# isp_02.net
KiCad netlist of a schematic drawn in EAGLE
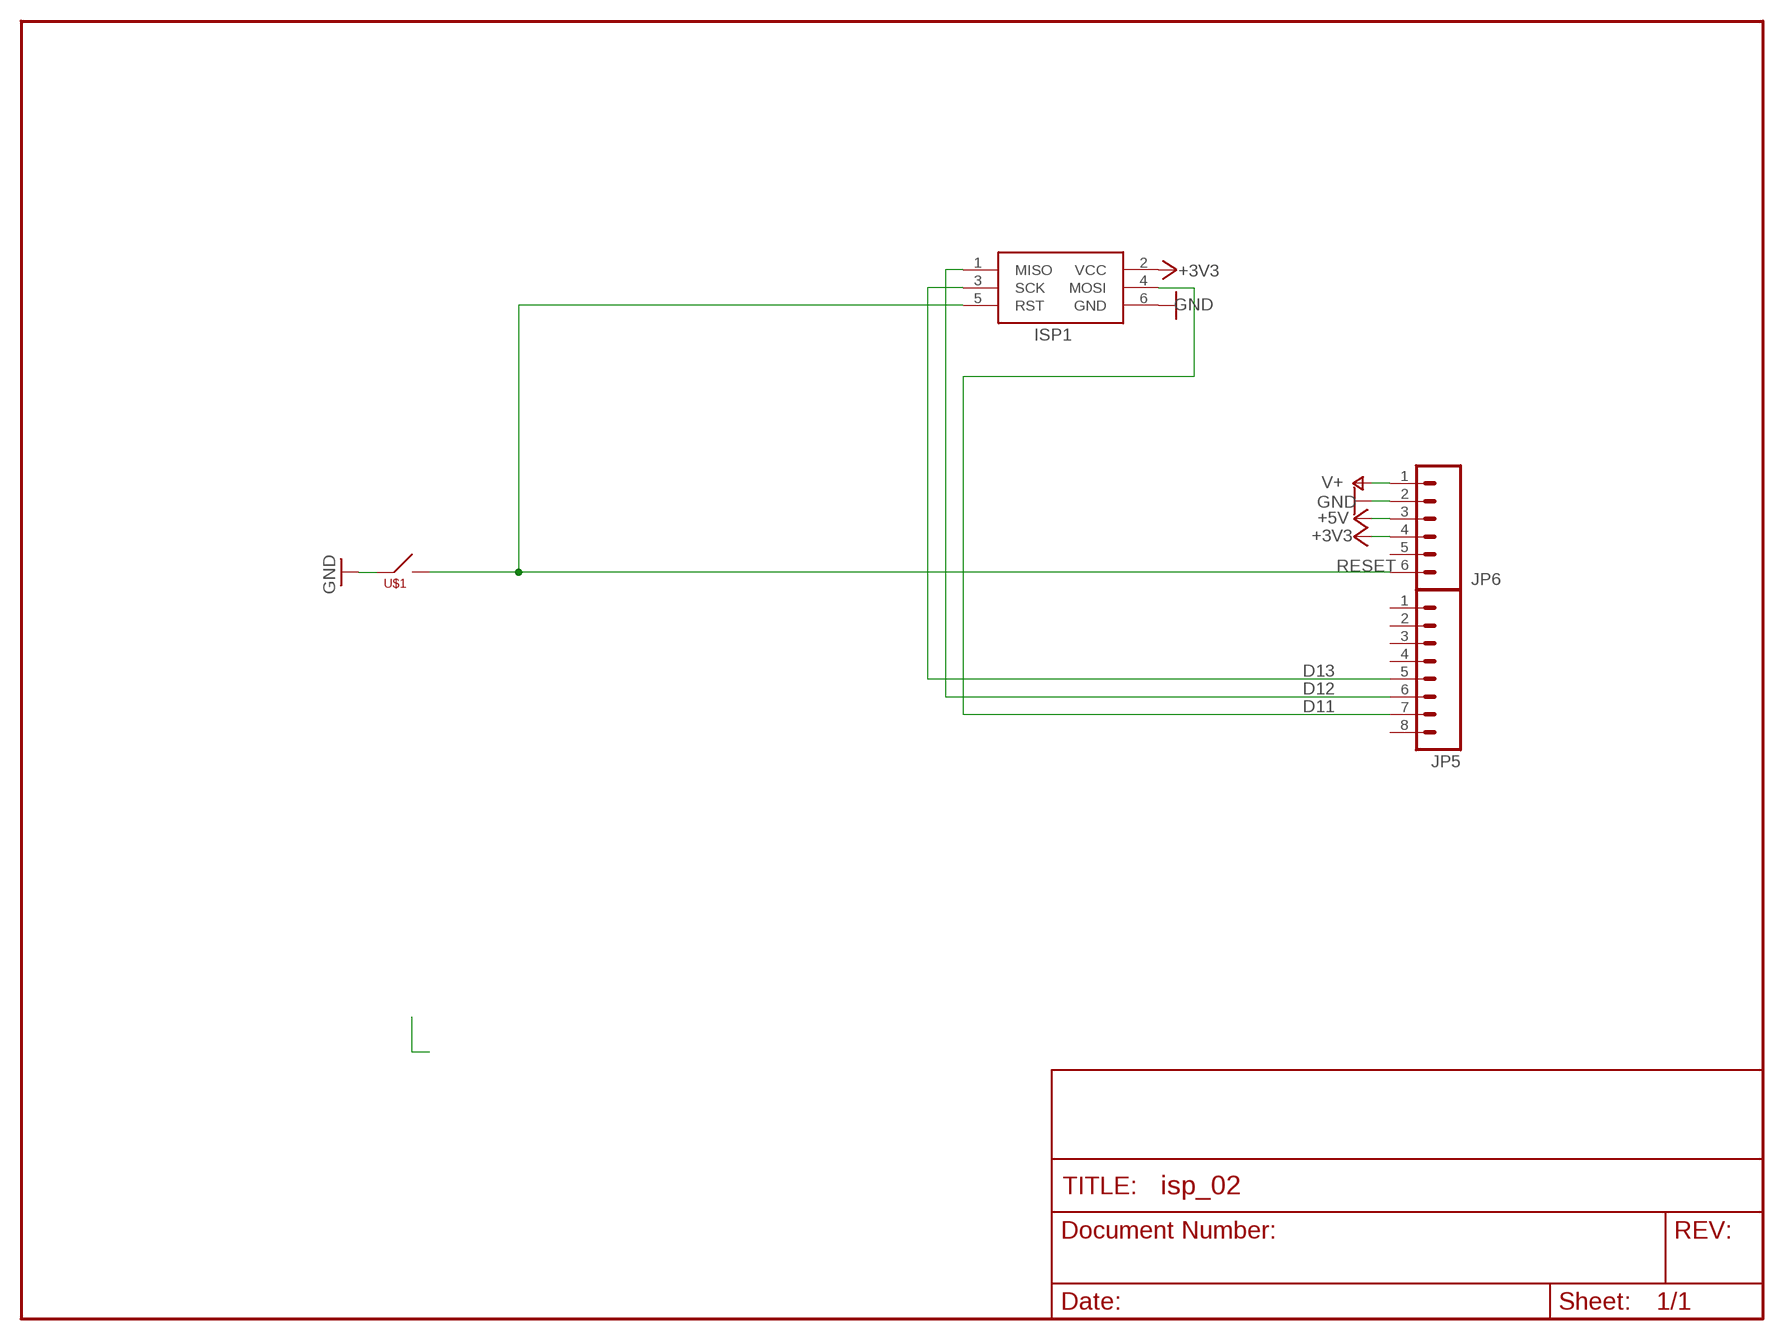
[diagram p0: schematic, sheet 1]

(export (version "E")
  (design (tool "Eeschema 10.0.6"))
  (components
    (comp (ref "ISP1")
      (value "AVRISP-6")
      (footprint "eagle-import:AVRISP")
      (libsource (lib "eagle-import") (part "AVRISP-6"))
    )
    (comp (ref "JP5")
      (value "M081X08")
      (footprint "eagle-import:1X08")
      (libsource (lib "eagle-import") (part "M081X08"))
    )
    (comp (ref "JP6")
      (value "M06SIP")
      (footprint "eagle-import:1X06")
      (libsource (lib "eagle-import") (part "M06SIP"))
    )
    (comp (ref "U$1")
      (value "PTS635_SWITCH")
      (footprint "eagle-import:PTS635_SWITCH")
      (libsource (lib "eagle-import") (part "PTS635_SWITCH"))
    )
  )
  (nets
    (net (code "1") (name "+3V3") (class "Default")
      (node (ref "ISP1") (pin "2") (pinfunction "VCC_2") (pintype "power_in"))
      (node (ref "JP6") (pin "4") (pinfunction "4_4") (pintype "passive"))
    )
    (net (code "2") (name "+5V") (class "Default")
      (node (ref "JP6") (pin "3") (pinfunction "3_3") (pintype "passive"))
    )
    (net (code "3") (name "/D11") (class "Default")
      (node (ref "ISP1") (pin "4") (pinfunction "MOSI_4") (pintype "output"))
      (node (ref "JP5") (pin "7") (pinfunction "7_7") (pintype "passive"))
    )
    (net (code "4") (name "/D12") (class "Default")
      (node (ref "ISP1") (pin "1") (pinfunction "MISO_1") (pintype "input"))
      (node (ref "JP5") (pin "6") (pinfunction "6_6") (pintype "passive"))
    )
    (net (code "5") (name "/D13") (class "Default")
      (node (ref "ISP1") (pin "3") (pinfunction "SCK_3") (pintype "output"))
      (node (ref "JP5") (pin "5") (pinfunction "5_5") (pintype "passive"))
    )
    (net (code "6") (name "/RESET") (class "Default")
      (node (ref "ISP1") (pin "5") (pinfunction "RST_5") (pintype "output"))
      (node (ref "JP6") (pin "6") (pinfunction "6_6") (pintype "passive"))
      (node (ref "U$1") (pin "P$2") (pinfunction "P$2_P$2") (pintype "bidirectional"))
    )
    (net (code "7") (name "GND") (class "Default")
      (node (ref "ISP1") (pin "6") (pinfunction "GND_6") (pintype "power_in"))
      (node (ref "JP6") (pin "2") (pinfunction "2_2") (pintype "passive"))
      (node (ref "U$1") (pin "P$1") (pinfunction "P$1_P$1") (pintype "bidirectional"))
    )
    (net (code "8") (name "V+") (class "Default")
      (node (ref "JP6") (pin "1") (pinfunction "1_1") (pintype "passive"))
    )
    (net (code "9") (name "unconnected-(JP5-Pad1)") (class "Default")
      (node (ref "JP5") (pin "1") (pinfunction "1_1") (pintype "passive"))
    )
    (net (code "10") (name "unconnected-(JP5-Pad2)") (class "Default")
      (node (ref "JP5") (pin "2") (pinfunction "2_2") (pintype "passive"))
    )
    (net (code "11") (name "unconnected-(JP5-Pad3)") (class "Default")
      (node (ref "JP5") (pin "3") (pinfunction "3_3") (pintype "passive"))
    )
    (net (code "12") (name "unconnected-(JP5-Pad4)") (class "Default")
      (node (ref "JP5") (pin "4") (pinfunction "4_4") (pintype "passive"))
    )
    (net (code "13") (name "unconnected-(JP5-Pad8)") (class "Default")
      (node (ref "JP5") (pin "8") (pinfunction "8_8") (pintype "passive"))
    )
    (net (code "14") (name "unconnected-(JP6-Pad5)") (class "Default")
      (node (ref "JP6") (pin "5") (pinfunction "5_5") (pintype "passive"))
    )
  )
)
